# Targets_old1.net
KiCad netlist of a schematic drawn in Altium Designer
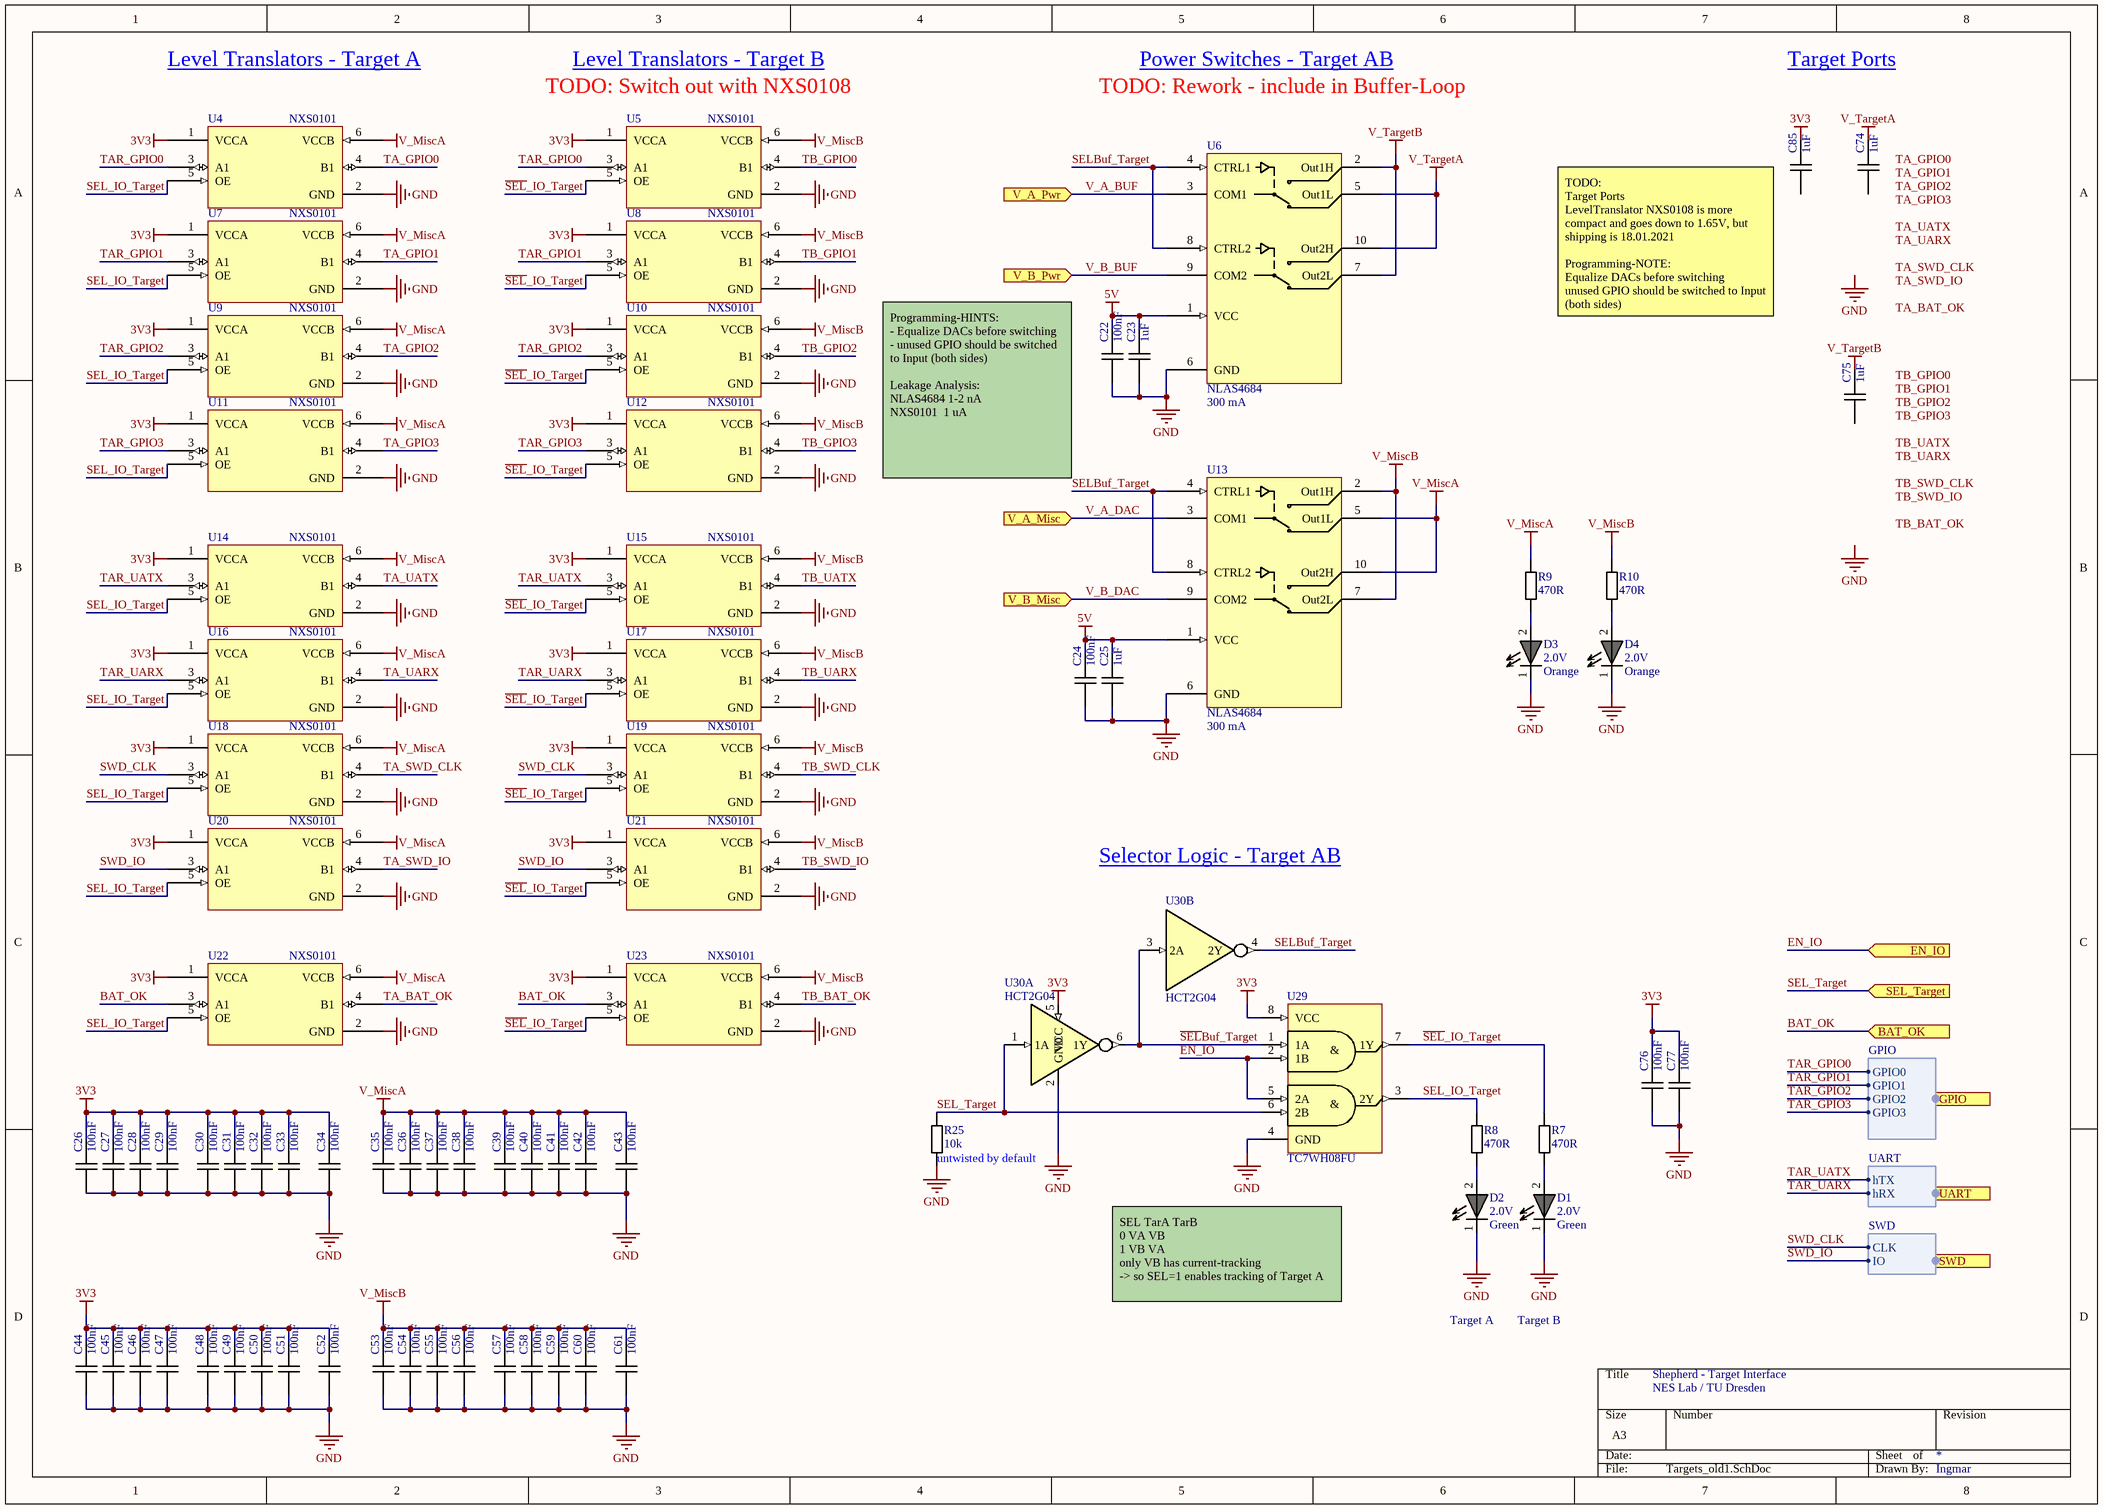
[diagram p0: Targets_old1.SchDoc]

(export (version "E")
  (design (tool "Eeschema 10.0.6"))
  (components
    (comp (ref "C22")
      (value "100nF")
      (footprint "CAPC1005X06")
      (description "Capacitor")
      (fields (field (name "MANUFACTURER") "Murata") (field (name "TOLERANCE") "10%"))
      (libsource (lib "shepherd_parts") (part ".C_0402_100nF_10V"))
    )
    (comp (ref "C23")
      (value "1uF")
      (footprint "CAPC1608X09")
      (description "Capacitor")
      (fields (field (name "MANUFACTURER") "KEMET") (field (name "TOLERANCE") "10%"))
      (libsource (lib "shepherd_parts") (part ".C_0603_1uF_10V"))
    )
    (comp (ref "C24")
      (value "100nF")
      (footprint "CAPC1005X06")
      (description "Capacitor")
      (fields (field (name "MANUFACTURER") "Murata") (field (name "TOLERANCE") "10%"))
      (libsource (lib "shepherd_parts") (part ".C_0402_100nF_10V"))
    )
    (comp (ref "C25")
      (value "1uF")
      (footprint "CAPC1608X09")
      (description "Capacitor")
      (fields (field (name "MANUFACTURER") "KEMET") (field (name "TOLERANCE") "10%"))
      (libsource (lib "shepherd_parts") (part ".C_0603_1uF_10V"))
    )
    (comp (ref "C26")
      (value "100nF")
      (footprint "CAPC1005X06")
      (description "Capacitor")
      (fields (field (name "MANUFACTURER") "Murata") (field (name "TOLERANCE") "10%"))
      (libsource (lib "shepherd_parts") (part ".C_0402_100nF_10V"))
    )
    (comp (ref "C27")
      (value "100nF")
      (footprint "CAPC1005X06")
      (description "Capacitor")
      (fields (field (name "MANUFACTURER") "Murata") (field (name "TOLERANCE") "10%"))
      (libsource (lib "shepherd_parts") (part ".C_0402_100nF_10V"))
    )
    (comp (ref "C28")
      (value "100nF")
      (footprint "CAPC1005X06")
      (description "Capacitor")
      (fields (field (name "MANUFACTURER") "Murata") (field (name "TOLERANCE") "10%"))
      (libsource (lib "shepherd_parts") (part ".C_0402_100nF_10V"))
    )
    (comp (ref "C29")
      (value "100nF")
      (footprint "CAPC1005X06")
      (description "Capacitor")
      (fields (field (name "MANUFACTURER") "Murata") (field (name "TOLERANCE") "10%"))
      (libsource (lib "shepherd_parts") (part ".C_0402_100nF_10V"))
    )
    (comp (ref "C30")
      (value "100nF")
      (footprint "CAPC1005X06")
      (description "Capacitor")
      (fields (field (name "MANUFACTURER") "Murata") (field (name "TOLERANCE") "10%"))
      (libsource (lib "shepherd_parts") (part ".C_0402_100nF_10V"))
    )
    (comp (ref "C31")
      (value "100nF")
      (footprint "CAPC1005X06")
      (description "Capacitor")
      (fields (field (name "MANUFACTURER") "Murata") (field (name "TOLERANCE") "10%"))
      (libsource (lib "shepherd_parts") (part ".C_0402_100nF_10V"))
    )
    (comp (ref "C32")
      (value "100nF")
      (footprint "CAPC1005X06")
      (description "Capacitor")
      (fields (field (name "MANUFACTURER") "Murata") (field (name "TOLERANCE") "10%"))
      (libsource (lib "shepherd_parts") (part ".C_0402_100nF_10V"))
    )
    (comp (ref "C33")
      (value "100nF")
      (footprint "CAPC1005X06")
      (description "Capacitor")
      (fields (field (name "MANUFACTURER") "Murata") (field (name "TOLERANCE") "10%"))
      (libsource (lib "shepherd_parts") (part ".C_0402_100nF_10V"))
    )
    (comp (ref "C34")
      (value "100nF")
      (footprint "CAPC1005X06")
      (description "Capacitor")
      (fields (field (name "MANUFACTURER") "Murata") (field (name "TOLERANCE") "10%"))
      (libsource (lib "shepherd_parts") (part ".C_0402_100nF_10V"))
    )
    (comp (ref "C35")
      (value "100nF")
      (footprint "CAPC1005X06")
      (description "Capacitor")
      (fields (field (name "MANUFACTURER") "Murata") (field (name "TOLERANCE") "10%"))
      (libsource (lib "shepherd_parts") (part ".C_0402_100nF_10V"))
    )
    (comp (ref "C36")
      (value "100nF")
      (footprint "CAPC1005X06")
      (description "Capacitor")
      (fields (field (name "MANUFACTURER") "Murata") (field (name "TOLERANCE") "10%"))
      (libsource (lib "shepherd_parts") (part ".C_0402_100nF_10V"))
    )
    (comp (ref "C37")
      (value "100nF")
      (footprint "CAPC1005X06")
      (description "Capacitor")
      (fields (field (name "MANUFACTURER") "Murata") (field (name "TOLERANCE") "10%"))
      (libsource (lib "shepherd_parts") (part ".C_0402_100nF_10V"))
    )
    (comp (ref "C38")
      (value "100nF")
      (footprint "CAPC1005X06")
      (description "Capacitor")
      (fields (field (name "MANUFACTURER") "Murata") (field (name "TOLERANCE") "10%"))
      (libsource (lib "shepherd_parts") (part ".C_0402_100nF_10V"))
    )
    (comp (ref "C39")
      (value "100nF")
      (footprint "CAPC1005X06")
      (description "Capacitor")
      (fields (field (name "MANUFACTURER") "Murata") (field (name "TOLERANCE") "10%"))
      (libsource (lib "shepherd_parts") (part ".C_0402_100nF_10V"))
    )
    (comp (ref "C40")
      (value "100nF")
      (footprint "CAPC1005X06")
      (description "Capacitor")
      (fields (field (name "MANUFACTURER") "Murata") (field (name "TOLERANCE") "10%"))
      (libsource (lib "shepherd_parts") (part ".C_0402_100nF_10V"))
    )
    (comp (ref "C41")
      (value "100nF")
      (footprint "CAPC1005X06")
      (description "Capacitor")
      (fields (field (name "MANUFACTURER") "Murata") (field (name "TOLERANCE") "10%"))
      (libsource (lib "shepherd_parts") (part ".C_0402_100nF_10V"))
    )
    (comp (ref "C42")
      (value "100nF")
      (footprint "CAPC1005X06")
      (description "Capacitor")
      (fields (field (name "MANUFACTURER") "Murata") (field (name "TOLERANCE") "10%"))
      (libsource (lib "shepherd_parts") (part ".C_0402_100nF_10V"))
    )
    (comp (ref "C43")
      (value "100nF")
      (footprint "CAPC1005X06")
      (description "Capacitor")
      (fields (field (name "MANUFACTURER") "Murata") (field (name "TOLERANCE") "10%"))
      (libsource (lib "shepherd_parts") (part ".C_0402_100nF_10V"))
    )
    (comp (ref "C44")
      (value "100nF")
      (footprint "CAPC1005X06")
      (description "Capacitor")
      (fields (field (name "MANUFACTURER") "Murata") (field (name "TOLERANCE") "10%"))
      (libsource (lib "shepherd_parts") (part ".C_0402_100nF_10V"))
    )
    (comp (ref "C45")
      (value "100nF")
      (footprint "CAPC1005X06")
      (description "Capacitor")
      (fields (field (name "MANUFACTURER") "Murata") (field (name "TOLERANCE") "10%"))
      (libsource (lib "shepherd_parts") (part ".C_0402_100nF_10V"))
    )
    (comp (ref "C46")
      (value "100nF")
      (footprint "CAPC1005X06")
      (description "Capacitor")
      (fields (field (name "MANUFACTURER") "Murata") (field (name "TOLERANCE") "10%"))
      (libsource (lib "shepherd_parts") (part ".C_0402_100nF_10V"))
    )
    (comp (ref "C47")
      (value "100nF")
      (footprint "CAPC1005X06")
      (description "Capacitor")
      (fields (field (name "MANUFACTURER") "Murata") (field (name "TOLERANCE") "10%"))
      (libsource (lib "shepherd_parts") (part ".C_0402_100nF_10V"))
    )
    (comp (ref "C48")
      (value "100nF")
      (footprint "CAPC1005X06")
      (description "Capacitor")
      (fields (field (name "MANUFACTURER") "Murata") (field (name "TOLERANCE") "10%"))
      (libsource (lib "shepherd_parts") (part ".C_0402_100nF_10V"))
    )
    (comp (ref "C49")
      (value "100nF")
      (footprint "CAPC1005X06")
      (description "Capacitor")
      (fields (field (name "MANUFACTURER") "Murata") (field (name "TOLERANCE") "10%"))
      (libsource (lib "shepherd_parts") (part ".C_0402_100nF_10V"))
    )
    (comp (ref "C50")
      (value "100nF")
      (footprint "CAPC1005X06")
      (description "Capacitor")
      (fields (field (name "MANUFACTURER") "Murata") (field (name "TOLERANCE") "10%"))
      (libsource (lib "shepherd_parts") (part ".C_0402_100nF_10V"))
    )
    (comp (ref "C51")
      (value "100nF")
      (footprint "CAPC1005X06")
      (description "Capacitor")
      (fields (field (name "MANUFACTURER") "Murata") (field (name "TOLERANCE") "10%"))
      (libsource (lib "shepherd_parts") (part ".C_0402_100nF_10V"))
    )
    (comp (ref "C52")
      (value "100nF")
      (footprint "CAPC1005X06")
      (description "Capacitor")
      (fields (field (name "MANUFACTURER") "Murata") (field (name "TOLERANCE") "10%"))
      (libsource (lib "shepherd_parts") (part ".C_0402_100nF_10V"))
    )
    (comp (ref "C53")
      (value "100nF")
      (footprint "CAPC1005X06")
      (description "Capacitor")
      (fields (field (name "MANUFACTURER") "Murata") (field (name "TOLERANCE") "10%"))
      (libsource (lib "shepherd_parts") (part ".C_0402_100nF_10V"))
    )
    (comp (ref "C54")
      (value "100nF")
      (footprint "CAPC1005X06")
      (description "Capacitor")
      (fields (field (name "MANUFACTURER") "Murata") (field (name "TOLERANCE") "10%"))
      (libsource (lib "shepherd_parts") (part ".C_0402_100nF_10V"))
    )
    (comp (ref "C55")
      (value "100nF")
      (footprint "CAPC1005X06")
      (description "Capacitor")
      (fields (field (name "MANUFACTURER") "Murata") (field (name "TOLERANCE") "10%"))
      (libsource (lib "shepherd_parts") (part ".C_0402_100nF_10V"))
    )
    (comp (ref "C56")
      (value "100nF")
      (footprint "CAPC1005X06")
      (description "Capacitor")
      (fields (field (name "MANUFACTURER") "Murata") (field (name "TOLERANCE") "10%"))
      (libsource (lib "shepherd_parts") (part ".C_0402_100nF_10V"))
    )
    (comp (ref "C57")
      (value "100nF")
      (footprint "CAPC1005X06")
      (description "Capacitor")
      (fields (field (name "MANUFACTURER") "Murata") (field (name "TOLERANCE") "10%"))
      (libsource (lib "shepherd_parts") (part ".C_0402_100nF_10V"))
    )
    (comp (ref "C58")
      (value "100nF")
      (footprint "CAPC1005X06")
      (description "Capacitor")
      (fields (field (name "MANUFACTURER") "Murata") (field (name "TOLERANCE") "10%"))
      (libsource (lib "shepherd_parts") (part ".C_0402_100nF_10V"))
    )
    (comp (ref "C59")
      (value "100nF")
      (footprint "CAPC1005X06")
      (description "Capacitor")
      (fields (field (name "MANUFACTURER") "Murata") (field (name "TOLERANCE") "10%"))
      (libsource (lib "shepherd_parts") (part ".C_0402_100nF_10V"))
    )
    (comp (ref "C60")
      (value "100nF")
      (footprint "CAPC1005X06")
      (description "Capacitor")
      (fields (field (name "MANUFACTURER") "Murata") (field (name "TOLERANCE") "10%"))
      (libsource (lib "shepherd_parts") (part ".C_0402_100nF_10V"))
    )
    (comp (ref "C61")
      (value "100nF")
      (footprint "CAPC1005X06")
      (description "Capacitor")
      (fields (field (name "MANUFACTURER") "Murata") (field (name "TOLERANCE") "10%"))
      (libsource (lib "shepherd_parts") (part ".C_0402_100nF_10V"))
    )
    (comp (ref "C74")
      (value "1uF")
      (footprint "CAPC1608X09")
      (description "Capacitor")
      (fields (field (name "MANUFACTURER") "KEMET") (field (name "TOLERANCE") "10%"))
      (libsource (lib "shepherd_parts") (part ".C_0603_1uF_10V"))
    )
    (comp (ref "C75")
      (value "1uF")
      (footprint "CAPC1608X09")
      (description "Capacitor")
      (fields (field (name "MANUFACTURER") "KEMET") (field (name "TOLERANCE") "10%"))
      (libsource (lib "shepherd_parts") (part ".C_0603_1uF_10V"))
    )
    (comp (ref "C76")
      (value "100nF")
      (footprint "CAPC1005X06")
      (description "Capacitor")
      (fields (field (name "MANUFACTURER") "Murata") (field (name "TOLERANCE") "10%"))
      (libsource (lib "shepherd_parts") (part ".C_0402_100nF_10V"))
    )
    (comp (ref "C77")
      (value "100nF")
      (footprint "CAPC1005X06")
      (description "Capacitor")
      (fields (field (name "MANUFACTURER") "Murata") (field (name "TOLERANCE") "10%"))
      (libsource (lib "shepherd_parts") (part ".C_0402_100nF_10V"))
    )
    (comp (ref "C85")
      (value "1uF")
      (footprint "CAPC1608X09")
      (description "Capacitor")
      (fields (field (name "MANUFACTURER") "KEMET") (field (name "TOLERANCE") "10%"))
      (libsource (lib "shepherd_parts") (part ".C_0603_1uF_10V"))
    )
    (comp (ref "D1")
      (value "Green")
      (footprint "DIOM1608X02N Green")
      (description "LED YellowGreen 575nm, 0603, 60mcd 2V@20mA")
      (fields
        (field (name "MANUFACTURER") "Wuerth")
        (field (name "V_MAX") "2.0V")
        (field (name "Comment") ".D_LED_0603_Green")
      )
      (libsource (lib "shepherd_parts") (part ".D_LED_0603_Green"))
    )
    (comp (ref "D2")
      (value "Green")
      (footprint "DIOM1608X02N Green")
      (description "LED YellowGreen 575nm, 0603, 60mcd 2V@20mA")
      (fields
        (field (name "MANUFACTURER") "Wuerth")
        (field (name "V_MAX") "2.0V")
        (field (name "Comment") ".D_LED_0603_Green")
      )
      (libsource (lib "shepherd_parts") (part ".D_LED_0603_Green"))
    )
    (comp (ref "D3")
      (value "Orange")
      (footprint "DIOM1608X02N Orange")
      (description "LED RedOrange 632nm, 0603, 90 mcd, 2V@20mA")
      (fields
        (field (name "MANUFACTURER") "Wuerth")
        (field (name "V_MAX") "2.0V")
        (field (name "Comment") ".D_LED_0603_Orange")
      )
      (libsource (lib "shepherd_parts") (part ".D_LED_0603_Orange"))
    )
    (comp (ref "D4")
      (value "Orange")
      (footprint "DIOM1608X02N Orange")
      (description "LED RedOrange 632nm, 0603, 90 mcd, 2V@20mA")
      (fields
        (field (name "MANUFACTURER") "Wuerth")
        (field (name "V_MAX") "2.0V")
        (field (name "Comment") ".D_LED_0603_Orange")
      )
      (libsource (lib "shepherd_parts") (part ".D_LED_0603_Orange"))
    )
    (comp (ref "R7")
      (value "470R")
      (footprint "RESC1005X04")
      (description "Resistor")
      (fields (field (name "MANUFACTURER") "Panasonic") (field (name "TOLERANCE") "5%"))
      (libsource (lib "shepherd_parts") (part ".R_0402_470R"))
    )
    (comp (ref "R8")
      (value "470R")
      (footprint "RESC1005X04")
      (description "Resistor")
      (fields (field (name "MANUFACTURER") "Panasonic") (field (name "TOLERANCE") "5%"))
      (libsource (lib "shepherd_parts") (part ".R_0402_470R"))
    )
    (comp (ref "R9")
      (value "470R")
      (footprint "RESC1005X04")
      (description "Resistor")
      (fields (field (name "MANUFACTURER") "Panasonic") (field (name "TOLERANCE") "5%"))
      (libsource (lib "shepherd_parts") (part ".R_0402_470R"))
    )
    (comp (ref "R10")
      (value "470R")
      (footprint "RESC1005X04")
      (description "Resistor")
      (fields (field (name "MANUFACTURER") "Panasonic") (field (name "TOLERANCE") "5%"))
      (libsource (lib "shepherd_parts") (part ".R_0402_470R"))
    )
    (comp (ref "R25")
      (value "10k")
      (footprint "RESC1005X04")
      (description "Resistor")
      (fields (field (name "MANUFACTURER") "Panasonic") (field (name "TOLERANCE") "5%"))
      (libsource (lib "shepherd_parts") (part ".R_0402_10k"))
    )
    (comp (ref "U4")
      (value "NXS0101")
      (footprint "SON50P100X50-6N SOT886")
      (fields (field (name "MANUFACTURER") "Nexperia"))
      (libsource (lib "shepherd_parts") (part "NXS0101"))
    )
    (comp (ref "U5")
      (value "NXS0101")
      (footprint "SON50P100X50-6N SOT886")
      (fields (field (name "MANUFACTURER") "Nexperia"))
      (libsource (lib "shepherd_parts") (part "NXS0101"))
    )
    (comp (ref "U6")
      (value "NLAS4684")
      (footprint "PSON50P300X100_HS-11N")
      (description "Analog Switch, Dual SPDT, 500 mOhm Rds, 300 mA continuous, 500 mA peak, <10 nA Leakage")
      (fields (field (name "MANUFACTURER") "ON Semi") (field (name "I_MAX") "300 mA"))
      (libsource (lib "shepherd_parts") (part "NLAS4684-MN"))
    )
    (comp (ref "U7")
      (value "NXS0101")
      (footprint "SON50P100X50-6N SOT886")
      (fields (field (name "MANUFACTURER") "Nexperia"))
      (libsource (lib "shepherd_parts") (part "NXS0101"))
    )
    (comp (ref "U8")
      (value "NXS0101")
      (footprint "SON50P100X50-6N SOT886")
      (fields (field (name "MANUFACTURER") "Nexperia"))
      (libsource (lib "shepherd_parts") (part "NXS0101"))
    )
    (comp (ref "U9")
      (value "NXS0101")
      (footprint "SON50P100X50-6N SOT886")
      (fields (field (name "MANUFACTURER") "Nexperia"))
      (libsource (lib "shepherd_parts") (part "NXS0101"))
    )
    (comp (ref "U10")
      (value "NXS0101")
      (footprint "SON50P100X50-6N SOT886")
      (fields (field (name "MANUFACTURER") "Nexperia"))
      (libsource (lib "shepherd_parts") (part "NXS0101"))
    )
    (comp (ref "U11")
      (value "NXS0101")
      (footprint "SON50P100X50-6N SOT886")
      (fields (field (name "MANUFACTURER") "Nexperia"))
      (libsource (lib "shepherd_parts") (part "NXS0101"))
    )
    (comp (ref "U12")
      (value "NXS0101")
      (footprint "SON50P100X50-6N SOT886")
      (fields (field (name "MANUFACTURER") "Nexperia"))
      (libsource (lib "shepherd_parts") (part "NXS0101"))
    )
    (comp (ref "U13")
      (value "NLAS4684")
      (footprint "PSON50P300X100_HS-11N")
      (description "Analog Switch, Dual SPDT, 500 mOhm Rds, 300 mA continuous, 500 mA peak, <10 nA Leakage")
      (fields (field (name "MANUFACTURER") "ON Semi") (field (name "I_MAX") "300 mA"))
      (libsource (lib "shepherd_parts") (part "NLAS4684-MN"))
    )
    (comp (ref "U14")
      (value "NXS0101")
      (footprint "SON50P100X50-6N SOT886")
      (fields (field (name "MANUFACTURER") "Nexperia"))
      (libsource (lib "shepherd_parts") (part "NXS0101"))
    )
    (comp (ref "U15")
      (value "NXS0101")
      (footprint "SON50P100X50-6N SOT886")
      (fields (field (name "MANUFACTURER") "Nexperia"))
      (libsource (lib "shepherd_parts") (part "NXS0101"))
    )
    (comp (ref "U16")
      (value "NXS0101")
      (footprint "SON50P100X50-6N SOT886")
      (fields (field (name "MANUFACTURER") "Nexperia"))
      (libsource (lib "shepherd_parts") (part "NXS0101"))
    )
    (comp (ref "U17")
      (value "NXS0101")
      (footprint "SON50P100X50-6N SOT886")
      (fields (field (name "MANUFACTURER") "Nexperia"))
      (libsource (lib "shepherd_parts") (part "NXS0101"))
    )
    (comp (ref "U18")
      (value "NXS0101")
      (footprint "SON50P100X50-6N SOT886")
      (fields (field (name "MANUFACTURER") "Nexperia"))
      (libsource (lib "shepherd_parts") (part "NXS0101"))
    )
    (comp (ref "U19")
      (value "NXS0101")
      (footprint "SON50P100X50-6N SOT886")
      (fields (field (name "MANUFACTURER") "Nexperia"))
      (libsource (lib "shepherd_parts") (part "NXS0101"))
    )
    (comp (ref "U20")
      (value "NXS0101")
      (footprint "SON50P100X50-6N SOT886")
      (fields (field (name "MANUFACTURER") "Nexperia"))
      (libsource (lib "shepherd_parts") (part "NXS0101"))
    )
    (comp (ref "U21")
      (value "NXS0101")
      (footprint "SON50P100X50-6N SOT886")
      (fields (field (name "MANUFACTURER") "Nexperia"))
      (libsource (lib "shepherd_parts") (part "NXS0101"))
    )
    (comp (ref "U22")
      (value "NXS0101")
      (footprint "SON50P100X50-6N SOT886")
      (fields (field (name "MANUFACTURER") "Nexperia"))
      (libsource (lib "shepherd_parts") (part "NXS0101"))
    )
    (comp (ref "U23")
      (value "NXS0101")
      (footprint "SON50P100X50-6N SOT886")
      (fields (field (name "MANUFACTURER") "Nexperia"))
      (libsource (lib "shepherd_parts") (part "NXS0101"))
    )
    (comp (ref "U29")
      (value "TC7WH08FU")
      (footprint "TSOP65P400X120-8N")
      (description "Logic Gate, 2-Channel 2-Input AND Gate, 25 mA IOut max,")
      (fields (field (name "MANUFACTURER") "Toshiba"))
      (libsource (lib "shepherd_parts") (part "TC7WH08FU"))
    )
    (comp (ref "U30")
      (value "HCT2G04")
      (footprint "SOT65P210X110-6N")
      (description "Inverter Dual, Buffered, I_out +- 25mA max,")
      (fields (field (name "MANUFACTURER") "Nexperia"))
      (libsource (lib "shepherd_parts") (part "HCT2G04"))
    )
  )
  (nets
    (net (code "4") (name "/BAT_OK") (class "Default")
      (node (ref "U22") (pin "3") (pinfunction "A1_3") (pintype "bidirectional"))
      (node (ref "U23") (pin "3") (pinfunction "A1_3") (pintype "bidirectional"))
    )
    (net (code "5") (name "/EN_IO") (class "Default")
      (node (ref "U29") (pin "2") (pinfunction "1B_2") (pintype "input"))
      (node (ref "U29") (pin "5") (pinfunction "2A_5") (pintype "input"))
    )
    (net (code "6") (name "/SELBuf_Target") (class "Default")
      (node (ref "U13") (pin "4") (pinfunction "CTRL1_4") (pintype "input"))
      (node (ref "U13") (pin "8") (pinfunction "CTRL2_8") (pintype "input"))
      (node (ref "U30") (pin "4") (pinfunction "2Y_4") (pintype "output"))
      (node (ref "U6") (pin "4") (pinfunction "CTRL1_4") (pintype "input"))
      (node (ref "U6") (pin "8") (pinfunction "CTRL2_8") (pintype "input"))
    )
    (net (code "7") (name "/SEL_IO_Target") (class "Default")
      (node (ref "R8") (pin "2") (pinfunction "2_2") (pintype "passive"))
      (node (ref "U11") (pin "5") (pinfunction "OE_5") (pintype "input"))
      (node (ref "U14") (pin "5") (pinfunction "OE_5") (pintype "input"))
      (node (ref "U16") (pin "5") (pinfunction "OE_5") (pintype "input"))
      (node (ref "U18") (pin "5") (pinfunction "OE_5") (pintype "input"))
      (node (ref "U20") (pin "5") (pinfunction "OE_5") (pintype "input"))
      (node (ref "U22") (pin "5") (pinfunction "OE_5") (pintype "input"))
      (node (ref "U29") (pin "3") (pinfunction "2Y_3") (pintype "output"))
      (node (ref "U4") (pin "5") (pinfunction "OE_5") (pintype "input"))
      (node (ref "U7") (pin "5") (pinfunction "OE_5") (pintype "input"))
      (node (ref "U9") (pin "5") (pinfunction "OE_5") (pintype "input"))
    )
    (net (code "8") (name "/SEL_Target") (class "Default")
      (node (ref "R25") (pin "2") (pinfunction "2_2") (pintype "passive"))
      (node (ref "U29") (pin "6") (pinfunction "2B_6") (pintype "input"))
      (node (ref "U30") (pin "1") (pinfunction "1A_1") (pintype "input"))
    )
    (net (code "9") (name "/SWD_CLK") (class "Default")
      (node (ref "U18") (pin "3") (pinfunction "A1_3") (pintype "bidirectional"))
      (node (ref "U19") (pin "3") (pinfunction "A1_3") (pintype "bidirectional"))
    )
    (net (code "10") (name "/SWD_IO") (class "Default")
      (node (ref "U20") (pin "3") (pinfunction "A1_3") (pintype "bidirectional"))
      (node (ref "U21") (pin "3") (pinfunction "A1_3") (pintype "bidirectional"))
    )
    (net (code "11") (name "/TAR_GPIO0") (class "Default")
      (node (ref "U4") (pin "3") (pinfunction "A1_3") (pintype "bidirectional"))
      (node (ref "U5") (pin "3") (pinfunction "A1_3") (pintype "bidirectional"))
    )
    (net (code "12") (name "/TAR_GPIO1") (class "Default")
      (node (ref "U7") (pin "3") (pinfunction "A1_3") (pintype "bidirectional"))
      (node (ref "U8") (pin "3") (pinfunction "A1_3") (pintype "bidirectional"))
    )
    (net (code "13") (name "/TAR_GPIO2") (class "Default")
      (node (ref "U10") (pin "3") (pinfunction "A1_3") (pintype "bidirectional"))
      (node (ref "U9") (pin "3") (pinfunction "A1_3") (pintype "bidirectional"))
    )
    (net (code "14") (name "/TAR_GPIO3") (class "Default")
      (node (ref "U11") (pin "3") (pinfunction "A1_3") (pintype "bidirectional"))
      (node (ref "U12") (pin "3") (pinfunction "A1_3") (pintype "bidirectional"))
    )
    (net (code "15") (name "/TAR_UARX") (class "Default")
      (node (ref "U16") (pin "3") (pinfunction "A1_3") (pintype "bidirectional"))
      (node (ref "U17") (pin "3") (pinfunction "A1_3") (pintype "bidirectional"))
    )
    (net (code "16") (name "/TAR_UATX") (class "Default")
      (node (ref "U14") (pin "3") (pinfunction "A1_3") (pintype "bidirectional"))
      (node (ref "U15") (pin "3") (pinfunction "A1_3") (pintype "bidirectional"))
    )
    (net (code "17") (name "/TA_BAT_OK") (class "Default")
      (node (ref "U22") (pin "4") (pinfunction "B1_4") (pintype "bidirectional"))
    )
    (net (code "18") (name "/TA_GPIO0") (class "Default")
      (node (ref "U4") (pin "4") (pinfunction "B1_4") (pintype "bidirectional"))
    )
    (net (code "19") (name "/TA_GPIO1") (class "Default")
      (node (ref "U7") (pin "4") (pinfunction "B1_4") (pintype "bidirectional"))
    )
    (net (code "20") (name "/TA_GPIO2") (class "Default")
      (node (ref "U9") (pin "4") (pinfunction "B1_4") (pintype "bidirectional"))
    )
    (net (code "21") (name "/TA_GPIO3") (class "Default")
      (node (ref "U11") (pin "4") (pinfunction "B1_4") (pintype "bidirectional"))
    )
    (net (code "22") (name "/TA_SWD_CLK") (class "Default")
      (node (ref "U18") (pin "4") (pinfunction "B1_4") (pintype "bidirectional"))
    )
    (net (code "23") (name "/TA_SWD_IO") (class "Default")
      (node (ref "U20") (pin "4") (pinfunction "B1_4") (pintype "bidirectional"))
    )
    (net (code "24") (name "/TA_UARX") (class "Default")
      (node (ref "U16") (pin "4") (pinfunction "B1_4") (pintype "bidirectional"))
    )
    (net (code "25") (name "/TA_UATX") (class "Default")
      (node (ref "U14") (pin "4") (pinfunction "B1_4") (pintype "bidirectional"))
    )
    (net (code "26") (name "/TB_BAT_OK") (class "Default")
      (node (ref "U23") (pin "4") (pinfunction "B1_4") (pintype "bidirectional"))
    )
    (net (code "27") (name "/TB_GPIO0") (class "Default")
      (node (ref "U5") (pin "4") (pinfunction "B1_4") (pintype "bidirectional"))
    )
    (net (code "28") (name "/TB_GPIO1") (class "Default")
      (node (ref "U8") (pin "4") (pinfunction "B1_4") (pintype "bidirectional"))
    )
    (net (code "29") (name "/TB_GPIO2") (class "Default")
      (node (ref "U10") (pin "4") (pinfunction "B1_4") (pintype "bidirectional"))
    )
    (net (code "30") (name "/TB_GPIO3") (class "Default")
      (node (ref "U12") (pin "4") (pinfunction "B1_4") (pintype "bidirectional"))
    )
    (net (code "31") (name "/TB_SWD_CLK") (class "Default")
      (node (ref "U19") (pin "4") (pinfunction "B1_4") (pintype "bidirectional"))
    )
    (net (code "32") (name "/TB_SWD_IO") (class "Default")
      (node (ref "U21") (pin "4") (pinfunction "B1_4") (pintype "bidirectional"))
    )
    (net (code "33") (name "/TB_UARX") (class "Default")
      (node (ref "U17") (pin "4") (pinfunction "B1_4") (pintype "bidirectional"))
    )
    (net (code "34") (name "/TB_UATX") (class "Default")
      (node (ref "U15") (pin "4") (pinfunction "B1_4") (pintype "bidirectional"))
    )
    (net (code "35") (name "/V_A_BUF") (class "Default")
      (node (ref "U6") (pin "3") (pinfunction "COM1_3") (pintype "power_in"))
    )
    (net (code "36") (name "/V_A_DAC") (class "Default")
      (node (ref "U13") (pin "3") (pinfunction "COM1_3") (pintype "power_in"))
    )
    (net (code "37") (name "/V_B_BUF") (class "Default")
      (node (ref "U6") (pin "9") (pinfunction "COM2_9") (pintype "power_in"))
    )
    (net (code "38") (name "/V_B_DAC") (class "Default")
      (node (ref "U13") (pin "9") (pinfunction "COM2_9") (pintype "power_in"))
    )
    (net (code "42") (name "/~{SEL}Buf_Target") (class "Default")
      (node (ref "U29") (pin "1") (pinfunction "1A_1") (pintype "input"))
      (node (ref "U30") (pin "3") (pinfunction "2A_3") (pintype "input"))
      (node (ref "U30") (pin "6") (pinfunction "1Y_6") (pintype "output"))
    )
    (net (code "43") (name "/~{SEL}_IO_Target") (class "Default")
      (node (ref "R7") (pin "2") (pinfunction "2_2") (pintype "passive"))
      (node (ref "U10") (pin "5") (pinfunction "OE_5") (pintype "input"))
      (node (ref "U12") (pin "5") (pinfunction "OE_5") (pintype "input"))
      (node (ref "U15") (pin "5") (pinfunction "OE_5") (pintype "input"))
      (node (ref "U17") (pin "5") (pinfunction "OE_5") (pintype "input"))
      (node (ref "U19") (pin "5") (pinfunction "OE_5") (pintype "input"))
      (node (ref "U21") (pin "5") (pinfunction "OE_5") (pintype "input"))
      (node (ref "U23") (pin "5") (pinfunction "OE_5") (pintype "input"))
      (node (ref "U29") (pin "7") (pinfunction "1Y_7") (pintype "output"))
      (node (ref "U5") (pin "5") (pinfunction "OE_5") (pintype "input"))
      (node (ref "U8") (pin "5") (pinfunction "OE_5") (pintype "input"))
    )
    (net (code "44") (name "3V3") (class "Default")
      (node (ref "C26") (pin "2") (pinfunction "2_2") (pintype "passive"))
      (node (ref "C27") (pin "2") (pinfunction "2_2") (pintype "passive"))
      (node (ref "C28") (pin "2") (pinfunction "2_2") (pintype "passive"))
      (node (ref "C29") (pin "2") (pinfunction "2_2") (pintype "passive"))
      (node (ref "C30") (pin "2") (pinfunction "2_2") (pintype "passive"))
      (node (ref "C31") (pin "2") (pinfunction "2_2") (pintype "passive"))
      (node (ref "C32") (pin "2") (pinfunction "2_2") (pintype "passive"))
      (node (ref "C33") (pin "2") (pinfunction "2_2") (pintype "passive"))
      (node (ref "C34") (pin "2") (pinfunction "2_2") (pintype "passive"))
      (node (ref "C44") (pin "2") (pinfunction "2_2") (pintype "passive"))
      (node (ref "C45") (pin "2") (pinfunction "2_2") (pintype "passive"))
      (node (ref "C46") (pin "2") (pinfunction "2_2") (pintype "passive"))
      (node (ref "C47") (pin "2") (pinfunction "2_2") (pintype "passive"))
      (node (ref "C48") (pin "2") (pinfunction "2_2") (pintype "passive"))
      (node (ref "C49") (pin "2") (pinfunction "2_2") (pintype "passive"))
      (node (ref "C50") (pin "2") (pinfunction "2_2") (pintype "passive"))
      (node (ref "C51") (pin "2") (pinfunction "2_2") (pintype "passive"))
      (node (ref "C52") (pin "2") (pinfunction "2_2") (pintype "passive"))
      (node (ref "C76") (pin "2") (pinfunction "2_2") (pintype "passive"))
      (node (ref "C77") (pin "2") (pinfunction "2_2") (pintype "passive"))
      (node (ref "C85") (pin "2") (pinfunction "2_2") (pintype "passive"))
      (node (ref "U10") (pin "1") (pinfunction "VCCA_1") (pintype "power_in"))
      (node (ref "U11") (pin "1") (pinfunction "VCCA_1") (pintype "power_in"))
      (node (ref "U12") (pin "1") (pinfunction "VCCA_1") (pintype "power_in"))
      (node (ref "U14") (pin "1") (pinfunction "VCCA_1") (pintype "power_in"))
      (node (ref "U15") (pin "1") (pinfunction "VCCA_1") (pintype "power_in"))
      (node (ref "U16") (pin "1") (pinfunction "VCCA_1") (pintype "power_in"))
      (node (ref "U17") (pin "1") (pinfunction "VCCA_1") (pintype "power_in"))
      (node (ref "U18") (pin "1") (pinfunction "VCCA_1") (pintype "power_in"))
      (node (ref "U19") (pin "1") (pinfunction "VCCA_1") (pintype "power_in"))
      (node (ref "U20") (pin "1") (pinfunction "VCCA_1") (pintype "power_in"))
      (node (ref "U21") (pin "1") (pinfunction "VCCA_1") (pintype "power_in"))
      (node (ref "U22") (pin "1") (pinfunction "VCCA_1") (pintype "power_in"))
      (node (ref "U23") (pin "1") (pinfunction "VCCA_1") (pintype "power_in"))
      (node (ref "U29") (pin "8") (pinfunction "VCC_8") (pintype "input"))
      (node (ref "U30") (pin "5") (pinfunction "VCC_5") (pintype "input"))
      (node (ref "U4") (pin "1") (pinfunction "VCCA_1") (pintype "power_in"))
      (node (ref "U5") (pin "1") (pinfunction "VCCA_1") (pintype "power_in"))
      (node (ref "U7") (pin "1") (pinfunction "VCCA_1") (pintype "power_in"))
      (node (ref "U8") (pin "1") (pinfunction "VCCA_1") (pintype "power_in"))
      (node (ref "U9") (pin "1") (pinfunction "VCCA_1") (pintype "power_in"))
    )
    (net (code "45") (name "5V") (class "Default")
      (node (ref "C22") (pin "2") (pinfunction "2_2") (pintype "passive"))
      (node (ref "C23") (pin "2") (pinfunction "2_2") (pintype "passive"))
      (node (ref "C24") (pin "2") (pinfunction "2_2") (pintype "passive"))
      (node (ref "C25") (pin "2") (pinfunction "2_2") (pintype "passive"))
      (node (ref "U13") (pin "1") (pinfunction "VCC_1") (pintype "input"))
      (node (ref "U6") (pin "1") (pinfunction "VCC_1") (pintype "input"))
    )
    (net (code "46") (name "GND") (class "Default")
      (node (ref "C22") (pin "1") (pinfunction "1_1") (pintype "passive"))
      (node (ref "C23") (pin "1") (pinfunction "1_1") (pintype "passive"))
      (node (ref "C24") (pin "1") (pinfunction "1_1") (pintype "passive"))
      (node (ref "C25") (pin "1") (pinfunction "1_1") (pintype "passive"))
      (node (ref "C26") (pin "1") (pinfunction "1_1") (pintype "passive"))
      (node (ref "C27") (pin "1") (pinfunction "1_1") (pintype "passive"))
      (node (ref "C28") (pin "1") (pinfunction "1_1") (pintype "passive"))
      (node (ref "C29") (pin "1") (pinfunction "1_1") (pintype "passive"))
      (node (ref "C30") (pin "1") (pinfunction "1_1") (pintype "passive"))
      (node (ref "C31") (pin "1") (pinfunction "1_1") (pintype "passive"))
      (node (ref "C32") (pin "1") (pinfunction "1_1") (pintype "passive"))
      (node (ref "C33") (pin "1") (pinfunction "1_1") (pintype "passive"))
      (node (ref "C34") (pin "1") (pinfunction "1_1") (pintype "passive"))
      (node (ref "C35") (pin "1") (pinfunction "1_1") (pintype "passive"))
      (node (ref "C36") (pin "1") (pinfunction "1_1") (pintype "passive"))
      (node (ref "C37") (pin "1") (pinfunction "1_1") (pintype "passive"))
      (node (ref "C38") (pin "1") (pinfunction "1_1") (pintype "passive"))
      (node (ref "C39") (pin "1") (pinfunction "1_1") (pintype "passive"))
      (node (ref "C40") (pin "1") (pinfunction "1_1") (pintype "passive"))
      (node (ref "C41") (pin "1") (pinfunction "1_1") (pintype "passive"))
      (node (ref "C42") (pin "1") (pinfunction "1_1") (pintype "passive"))
      (node (ref "C43") (pin "1") (pinfunction "1_1") (pintype "passive"))
      (node (ref "C44") (pin "1") (pinfunction "1_1") (pintype "passive"))
      (node (ref "C45") (pin "1") (pinfunction "1_1") (pintype "passive"))
      (node (ref "C46") (pin "1") (pinfunction "1_1") (pintype "passive"))
      (node (ref "C47") (pin "1") (pinfunction "1_1") (pintype "passive"))
      (node (ref "C48") (pin "1") (pinfunction "1_1") (pintype "passive"))
      (node (ref "C49") (pin "1") (pinfunction "1_1") (pintype "passive"))
      (node (ref "C50") (pin "1") (pinfunction "1_1") (pintype "passive"))
      (node (ref "C51") (pin "1") (pinfunction "1_1") (pintype "passive"))
      (node (ref "C52") (pin "1") (pinfunction "1_1") (pintype "passive"))
      (node (ref "C53") (pin "1") (pinfunction "1_1") (pintype "passive"))
      (node (ref "C54") (pin "1") (pinfunction "1_1") (pintype "passive"))
      (node (ref "C55") (pin "1") (pinfunction "1_1") (pintype "passive"))
      (node (ref "C56") (pin "1") (pinfunction "1_1") (pintype "passive"))
      (node (ref "C57") (pin "1") (pinfunction "1_1") (pintype "passive"))
      (node (ref "C58") (pin "1") (pinfunction "1_1") (pintype "passive"))
      (node (ref "C59") (pin "1") (pinfunction "1_1") (pintype "passive"))
      (node (ref "C60") (pin "1") (pinfunction "1_1") (pintype "passive"))
      (node (ref "C61") (pin "1") (pinfunction "1_1") (pintype "passive"))
      (node (ref "C76") (pin "1") (pinfunction "1_1") (pintype "passive"))
      (node (ref "C77") (pin "1") (pinfunction "1_1") (pintype "passive"))
      (node (ref "D1") (pin "1") (pinfunction "1_1") (pintype "passive"))
      (node (ref "D2") (pin "1") (pinfunction "1_1") (pintype "passive"))
      (node (ref "D3") (pin "1") (pinfunction "1_1") (pintype "passive"))
      (node (ref "D4") (pin "1") (pinfunction "1_1") (pintype "passive"))
      (node (ref "R25") (pin "1") (pinfunction "1_1") (pintype "passive"))
      (node (ref "U10") (pin "2") (pinfunction "GND_2") (pintype "power_in"))
      (node (ref "U11") (pin "2") (pinfunction "GND_2") (pintype "power_in"))
      (node (ref "U12") (pin "2") (pinfunction "GND_2") (pintype "power_in"))
      (node (ref "U13") (pin "6") (pinfunction "GND_6") (pintype "power_in"))
      (node (ref "U14") (pin "2") (pinfunction "GND_2") (pintype "power_in"))
      (node (ref "U15") (pin "2") (pinfunction "GND_2") (pintype "power_in"))
      (node (ref "U16") (pin "2") (pinfunction "GND_2") (pintype "power_in"))
      (node (ref "U17") (pin "2") (pinfunction "GND_2") (pintype "power_in"))
      (node (ref "U18") (pin "2") (pinfunction "GND_2") (pintype "power_in"))
      (node (ref "U19") (pin "2") (pinfunction "GND_2") (pintype "power_in"))
      (node (ref "U20") (pin "2") (pinfunction "GND_2") (pintype "power_in"))
      (node (ref "U21") (pin "2") (pinfunction "GND_2") (pintype "power_in"))
      (node (ref "U22") (pin "2") (pinfunction "GND_2") (pintype "power_in"))
      (node (ref "U23") (pin "2") (pinfunction "GND_2") (pintype "power_in"))
      (node (ref "U29") (pin "4") (pinfunction "GND_4") (pintype "power_in"))
      (node (ref "U30") (pin "2") (pinfunction "GND_2") (pintype "power_in"))
      (node (ref "U4") (pin "2") (pinfunction "GND_2") (pintype "power_in"))
      (node (ref "U5") (pin "2") (pinfunction "GND_2") (pintype "power_in"))
      (node (ref "U6") (pin "6") (pinfunction "GND_6") (pintype "power_in"))
      (node (ref "U7") (pin "2") (pinfunction "GND_2") (pintype "power_in"))
      (node (ref "U8") (pin "2") (pinfunction "GND_2") (pintype "power_in"))
      (node (ref "U9") (pin "2") (pinfunction "GND_2") (pintype "power_in"))
    )
    (net (code "47") (name "Net-(D1-Pad2)") (class "Default")
      (node (ref "D1") (pin "2") (pinfunction "2_2") (pintype "passive"))
      (node (ref "R7") (pin "1") (pinfunction "1_1") (pintype "passive"))
    )
    (net (code "48") (name "Net-(D2-Pad2)") (class "Default")
      (node (ref "D2") (pin "2") (pinfunction "2_2") (pintype "passive"))
      (node (ref "R8") (pin "1") (pinfunction "1_1") (pintype "passive"))
    )
    (net (code "49") (name "Net-(D3-Pad2)") (class "Default")
      (node (ref "D3") (pin "2") (pinfunction "2_2") (pintype "passive"))
      (node (ref "R9") (pin "1") (pinfunction "1_1") (pintype "passive"))
    )
    (net (code "50") (name "Net-(D4-Pad2)") (class "Default")
      (node (ref "D4") (pin "2") (pinfunction "2_2") (pintype "passive"))
      (node (ref "R10") (pin "1") (pinfunction "1_1") (pintype "passive"))
    )
    (net (code "51") (name "V_MiscA") (class "Default")
      (node (ref "C35") (pin "2") (pinfunction "2_2") (pintype "passive"))
      (node (ref "C36") (pin "2") (pinfunction "2_2") (pintype "passive"))
      (node (ref "C37") (pin "2") (pinfunction "2_2") (pintype "passive"))
      (node (ref "C38") (pin "2") (pinfunction "2_2") (pintype "passive"))
      (node (ref "C39") (pin "2") (pinfunction "2_2") (pintype "passive"))
      (node (ref "C40") (pin "2") (pinfunction "2_2") (pintype "passive"))
      (node (ref "C41") (pin "2") (pinfunction "2_2") (pintype "passive"))
      (node (ref "C42") (pin "2") (pinfunction "2_2") (pintype "passive"))
      (node (ref "C43") (pin "2") (pinfunction "2_2") (pintype "passive"))
      (node (ref "R9") (pin "2") (pinfunction "2_2") (pintype "passive"))
      (node (ref "U11") (pin "6") (pinfunction "VCCB_6") (pintype "input"))
      (node (ref "U13") (pin "10") (pinfunction "Out2H_10") (pintype "power_in"))
      (node (ref "U13") (pin "5") (pinfunction "Out1L_5") (pintype "power_in"))
      (node (ref "U14") (pin "6") (pinfunction "VCCB_6") (pintype "input"))
      (node (ref "U16") (pin "6") (pinfunction "VCCB_6") (pintype "input"))
      (node (ref "U18") (pin "6") (pinfunction "VCCB_6") (pintype "input"))
      (node (ref "U20") (pin "6") (pinfunction "VCCB_6") (pintype "input"))
      (node (ref "U22") (pin "6") (pinfunction "VCCB_6") (pintype "input"))
      (node (ref "U4") (pin "6") (pinfunction "VCCB_6") (pintype "input"))
      (node (ref "U7") (pin "6") (pinfunction "VCCB_6") (pintype "input"))
      (node (ref "U9") (pin "6") (pinfunction "VCCB_6") (pintype "input"))
    )
    (net (code "52") (name "V_MiscB") (class "Default")
      (node (ref "C53") (pin "2") (pinfunction "2_2") (pintype "passive"))
      (node (ref "C54") (pin "2") (pinfunction "2_2") (pintype "passive"))
      (node (ref "C55") (pin "2") (pinfunction "2_2") (pintype "passive"))
      (node (ref "C56") (pin "2") (pinfunction "2_2") (pintype "passive"))
      (node (ref "C57") (pin "2") (pinfunction "2_2") (pintype "passive"))
      (node (ref "C58") (pin "2") (pinfunction "2_2") (pintype "passive"))
      (node (ref "C59") (pin "2") (pinfunction "2_2") (pintype "passive"))
      (node (ref "C60") (pin "2") (pinfunction "2_2") (pintype "passive"))
      (node (ref "C61") (pin "2") (pinfunction "2_2") (pintype "passive"))
      (node (ref "R10") (pin "2") (pinfunction "2_2") (pintype "passive"))
      (node (ref "U10") (pin "6") (pinfunction "VCCB_6") (pintype "input"))
      (node (ref "U12") (pin "6") (pinfunction "VCCB_6") (pintype "input"))
      (node (ref "U13") (pin "2") (pinfunction "Out1H_2") (pintype "power_in"))
      (node (ref "U13") (pin "7") (pinfunction "Out2L_7") (pintype "power_in"))
      (node (ref "U15") (pin "6") (pinfunction "VCCB_6") (pintype "input"))
      (node (ref "U17") (pin "6") (pinfunction "VCCB_6") (pintype "input"))
      (node (ref "U19") (pin "6") (pinfunction "VCCB_6") (pintype "input"))
      (node (ref "U21") (pin "6") (pinfunction "VCCB_6") (pintype "input"))
      (node (ref "U23") (pin "6") (pinfunction "VCCB_6") (pintype "input"))
      (node (ref "U5") (pin "6") (pinfunction "VCCB_6") (pintype "input"))
      (node (ref "U8") (pin "6") (pinfunction "VCCB_6") (pintype "input"))
    )
    (net (code "53") (name "V_TargetA") (class "Default")
      (node (ref "C74") (pin "2") (pinfunction "2_2") (pintype "passive"))
      (node (ref "U6") (pin "10") (pinfunction "Out2H_10") (pintype "power_in"))
      (node (ref "U6") (pin "5") (pinfunction "Out1L_5") (pintype "power_in"))
    )
    (net (code "54") (name "V_TargetB") (class "Default")
      (node (ref "C75") (pin "2") (pinfunction "2_2") (pintype "passive"))
      (node (ref "U6") (pin "2") (pinfunction "Out1H_2") (pintype "power_in"))
      (node (ref "U6") (pin "7") (pinfunction "Out2L_7") (pintype "power_in"))
    )
    (net (code "55") (name "unconnected-(C74-Pad1)") (class "Default")
      (node (ref "C74") (pin "1") (pinfunction "1_1") (pintype "passive"))
    )
    (net (code "56") (name "unconnected-(C75-Pad1)") (class "Default")
      (node (ref "C75") (pin "1") (pinfunction "1_1") (pintype "passive"))
    )
    (net (code "57") (name "unconnected-(C85-Pad1)") (class "Default")
      (node (ref "C85") (pin "1") (pinfunction "1_1") (pintype "passive"))
    )
  )
)
